# LED-Platinen.net
KiCad netlist of a schematic drawn in EAGLE
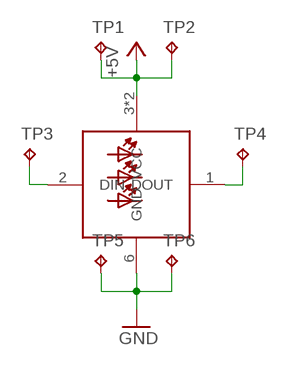
[diagram p0: schematic, sheet 1]

(export (version "E")
  (design (tool "Eeschema 10.0.6"))
  (components
    (comp (ref "TP1")
      (value "TPTP15SQ")
      (footprint "eagle-import:TP15SQ")
      (libsource (lib "eagle-import") (part "TPTP15SQ"))
    )
    (comp (ref "TP2")
      (value "TPTP15SQ")
      (footprint "eagle-import:TP15SQ")
      (libsource (lib "eagle-import") (part "TPTP15SQ"))
    )
    (comp (ref "TP3")
      (value "TPTP15SQ")
      (footprint "eagle-import:TP15SQ")
      (libsource (lib "eagle-import") (part "TPTP15SQ"))
    )
    (comp (ref "TP4")
      (value "TPTP15SQ")
      (footprint "eagle-import:TP15SQ")
      (libsource (lib "eagle-import") (part "TPTP15SQ"))
    )
    (comp (ref "TP5")
      (value "TPTP15SQ")
      (footprint "eagle-import:TP15SQ")
      (libsource (lib "eagle-import") (part "TPTP15SQ"))
    )
    (comp (ref "TP6")
      (value "TPTP15SQ")
      (footprint "eagle-import:TP15SQ")
      (libsource (lib "eagle-import") (part "TPTP15SQ"))
    )
    (comp (ref "U$1")
      (value "RGBLED")
      (footprint "eagle-import:RGBLED")
      (libsource (lib "eagle-import") (part "RGBLED"))
    )
  )
  (nets
    (net (code "1") (name "+5V") (class "Default")
      (node (ref "TP1") (pin "TP") (pinfunction "TP_TP") (pintype "input"))
      (node (ref "TP2") (pin "TP") (pinfunction "TP_TP") (pintype "input"))
      (node (ref "U$1") (pin "3") (pinfunction "VCC_3") (pintype "bidirectional"))
      (node (ref "U$1") (pin "5") (pinfunction "VCC_5") (pintype "bidirectional"))
    )
    (net (code "2") (name "GND") (class "Default")
      (node (ref "TP5") (pin "TP") (pinfunction "TP_TP") (pintype "input"))
      (node (ref "TP6") (pin "TP") (pinfunction "TP_TP") (pintype "input"))
      (node (ref "U$1") (pin "6") (pinfunction "GND_6") (pintype "bidirectional"))
    )
    (net (code "3") (name "Net-(U$1-DIN)") (class "Default")
      (node (ref "TP3") (pin "TP") (pinfunction "TP_TP") (pintype "input"))
      (node (ref "U$1") (pin "2") (pinfunction "DIN_2") (pintype "bidirectional"))
    )
    (net (code "4") (name "Net-(U$1-DOUT)") (class "Default")
      (node (ref "TP4") (pin "TP") (pinfunction "TP_TP") (pintype "input"))
      (node (ref "U$1") (pin "1") (pinfunction "DOUT_1") (pintype "bidirectional"))
    )
  )
)
